# DA_uno_shield_0_3.net
KiCad netlist of a schematic drawn in EAGLE
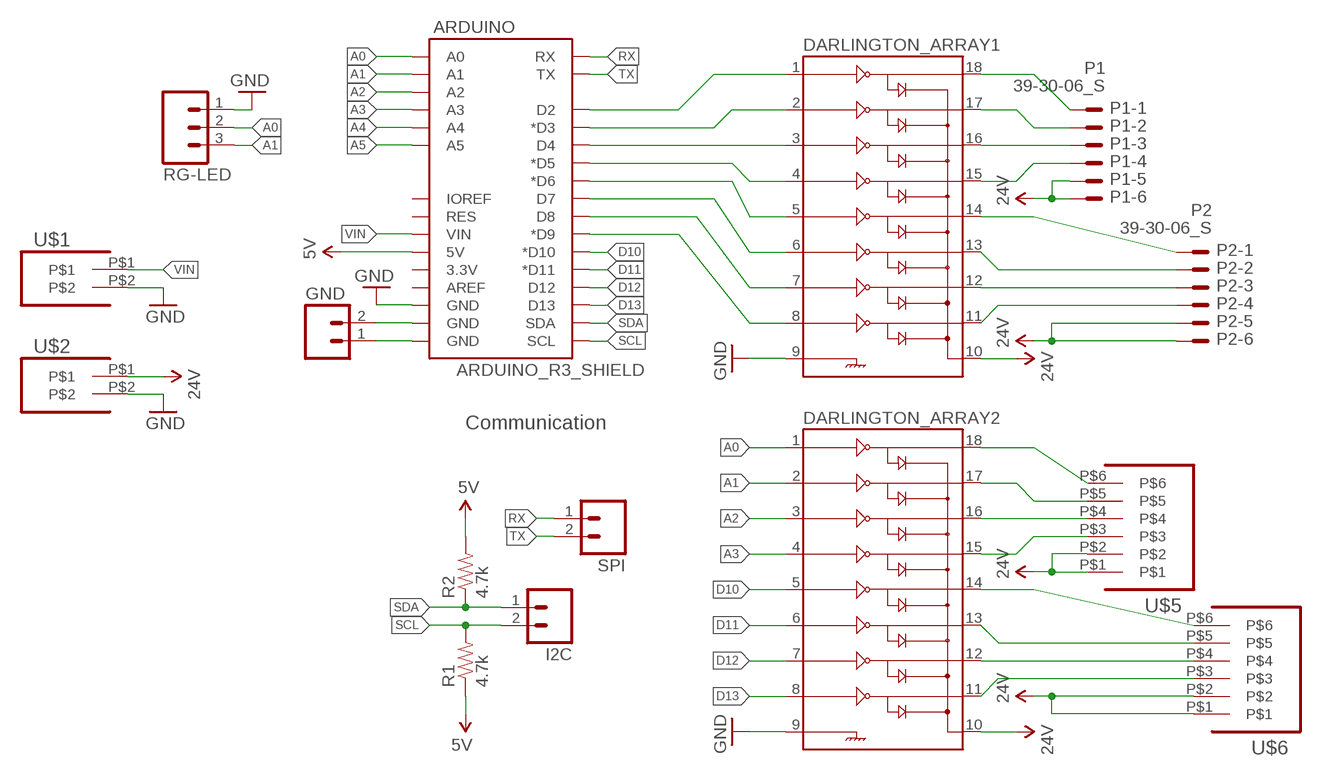
[diagram p0: schematic, sheet 1]

(export (version "E")
  (design (tool "Eeschema 10.0.6"))
  (components
    (comp (ref "ARDUINO")
      (value "ARDUINO_R3_SHIELD")
      (footprint "eagle-import:UNO_R3_SHIELD")
      (libsource (lib "eagle-import") (part "ARDUINO_R3_SHIELD"))
    )
    (comp (ref "DARLINGTON_ARRAY1")
      (value "ULN2803DIP")
      (footprint "eagle-import:DIL18")
      (libsource (lib "eagle-import") (part "ULN2803DIP"))
    )
    (comp (ref "DARLINGTON_ARRAY2")
      (value "ULN2803DIP")
      (footprint "eagle-import:DIL18")
      (libsource (lib "eagle-import") (part "ULN2803DIP"))
    )
    (comp (ref "GND")
      (value "M02LOCK_LONGPADS")
      (footprint "eagle-import:1X02_LOCK_LONGPADS")
      (libsource (lib "eagle-import") (part "M02LOCK_LONGPADS"))
    )
    (comp (ref "I2C")
      (value "M02LOCK_LONGPADS")
      (footprint "eagle-import:1X02_LOCK_LONGPADS")
      (libsource (lib "eagle-import") (part "M02LOCK_LONGPADS"))
    )
    (comp (ref "P1")
      (value "39-30-06_S")
      (footprint "eagle-import:39-30-_06_")
      (libsource (lib "eagle-import") (part "39-30-?06?_S"))
    )
    (comp (ref "P2")
      (value "39-30-06_S")
      (footprint "eagle-import:39-30-_06_")
      (libsource (lib "eagle-import") (part "39-30-?06?_S"))
    )
    (comp (ref "R1")
      (value "4.7k")
      (footprint "eagle-import:AXIAL-0.3-KIT")
      (libsource (lib "eagle-import") (part "RESISTORKIT"))
    )
    (comp (ref "R2")
      (value "4.7k")
      (footprint "eagle-import:AXIAL-0.3-KIT")
      (libsource (lib "eagle-import") (part "RESISTORKIT"))
    )
    (comp (ref "RG-LED")
      (value "M03LONGPADS")
      (footprint "eagle-import:1X03_LONGPADS")
      (libsource (lib "eagle-import") (part "M03LONGPADS"))
    )
    (comp (ref "SPI")
      (value "M02LOCK_LONGPADS")
      (footprint "eagle-import:1X02_LOCK_LONGPADS")
      (libsource (lib "eagle-import") (part "M02LOCK_LONGPADS"))
    )
    (comp (ref "U$1")
      (value "39-29-02")
      (footprint "eagle-import:39-29-_02_")
      (libsource (lib "eagle-import") (part "39-29-?02?"))
    )
    (comp (ref "U$2")
      (value "39-29-02")
      (footprint "eagle-import:39-29-_02_")
      (libsource (lib "eagle-import") (part "39-29-?02?"))
    )
    (comp (ref "U$5")
      (value "39-29-06")
      (footprint "eagle-import:39-29-_06_")
      (libsource (lib "eagle-import") (part "39-29-?06?"))
    )
    (comp (ref "U$6")
      (value "39-29-06")
      (footprint "eagle-import:39-29-_06_")
      (libsource (lib "eagle-import") (part "39-29-?06?"))
    )
  )
  (nets
    (net (code "1") (name "5V") (class "Default")
      (node (ref "ARDUINO") (pin "5V") (pinfunction "5V_5V") (pintype "bidirectional"))
      (node (ref "R1") (pin "P$1") (pinfunction "1_P$1") (pintype "passive"))
      (node (ref "R2") (pin "P$2") (pinfunction "2_P$2") (pintype "passive"))
    )
    (net (code "2") (name "24V") (class "Default")
      (node (ref "DARLINGTON_ARRAY1") (pin "10") (pinfunction "10_10") (pintype "bidirectional"))
      (node (ref "DARLINGTON_ARRAY2") (pin "10") (pinfunction "10_10") (pintype "bidirectional"))
      (node (ref "P1") (pin "5") (pinfunction "P_5") (pintype "passive"))
      (node (ref "P1") (pin "6") (pinfunction "P_6") (pintype "passive"))
      (node (ref "P2") (pin "5") (pinfunction "P_5") (pintype "passive"))
      (node (ref "P2") (pin "6") (pinfunction "P_6") (pintype "passive"))
      (node (ref "U$2") (pin "P$1") (pinfunction "P$1_P$1") (pintype "bidirectional"))
      (node (ref "U$5") (pin "P$1") (pinfunction "P$1_P$1") (pintype "bidirectional"))
      (node (ref "U$5") (pin "P$2") (pinfunction "P$2_P$2") (pintype "bidirectional"))
      (node (ref "U$6") (pin "P$1") (pinfunction "P$1_P$1") (pintype "bidirectional"))
      (node (ref "U$6") (pin "P$2") (pinfunction "P$2_P$2") (pintype "bidirectional"))
    )
    (net (code "3") (name "A0") (class "Default")
      (node (ref "ARDUINO") (pin "A0") (pinfunction "A0_A0") (pintype "bidirectional"))
      (node (ref "DARLINGTON_ARRAY2") (pin "1") (pinfunction "1_1") (pintype "bidirectional"))
      (node (ref "RG-LED") (pin "2") (pinfunction "2_2") (pintype "passive"))
    )
    (net (code "4") (name "A1") (class "Default")
      (node (ref "ARDUINO") (pin "A1") (pinfunction "A1_A1") (pintype "bidirectional"))
      (node (ref "DARLINGTON_ARRAY2") (pin "2") (pinfunction "2_2") (pintype "bidirectional"))
      (node (ref "RG-LED") (pin "3") (pinfunction "3_3") (pintype "passive"))
    )
    (net (code "5") (name "A2") (class "Default")
      (node (ref "ARDUINO") (pin "A2") (pinfunction "A2_A2") (pintype "bidirectional"))
      (node (ref "DARLINGTON_ARRAY2") (pin "3") (pinfunction "3_3") (pintype "bidirectional"))
    )
    (net (code "6") (name "A3") (class "Default")
      (node (ref "ARDUINO") (pin "A3") (pinfunction "A3_A3") (pintype "bidirectional"))
      (node (ref "DARLINGTON_ARRAY2") (pin "4") (pinfunction "4_4") (pintype "bidirectional"))
    )
    (net (code "7") (name "A4") (class "Default")
      (node (ref "ARDUINO") (pin "A4") (pinfunction "A4_A4") (pintype "bidirectional"))
    )
    (net (code "8") (name "A5") (class "Default")
      (node (ref "ARDUINO") (pin "A5") (pinfunction "A5_A5") (pintype "bidirectional"))
    )
    (net (code "9") (name "D10") (class "Default")
      (node (ref "ARDUINO") (pin "D10") (pinfunction "*D10_D10") (pintype "bidirectional"))
      (node (ref "DARLINGTON_ARRAY2") (pin "5") (pinfunction "5_5") (pintype "bidirectional"))
    )
    (net (code "10") (name "D11") (class "Default")
      (node (ref "ARDUINO") (pin "D11") (pinfunction "*D11_D11") (pintype "bidirectional"))
      (node (ref "DARLINGTON_ARRAY2") (pin "6") (pinfunction "6_6") (pintype "bidirectional"))
    )
    (net (code "11") (name "D12") (class "Default")
      (node (ref "ARDUINO") (pin "D12") (pinfunction "D12_D12") (pintype "bidirectional"))
      (node (ref "DARLINGTON_ARRAY2") (pin "7") (pinfunction "7_7") (pintype "bidirectional"))
    )
    (net (code "12") (name "D13") (class "Default")
      (node (ref "ARDUINO") (pin "D13") (pinfunction "D13_D13") (pintype "bidirectional"))
      (node (ref "DARLINGTON_ARRAY2") (pin "8") (pinfunction "8_8") (pintype "bidirectional"))
    )
    (net (code "13") (name "GND") (class "Default")
      (node (ref "ARDUINO") (pin "GND@2") (pinfunction "GND_GND@2") (pintype "bidirectional"))
      (node (ref "DARLINGTON_ARRAY1") (pin "9") (pinfunction "9_9") (pintype "bidirectional"))
      (node (ref "DARLINGTON_ARRAY2") (pin "9") (pinfunction "9_9") (pintype "bidirectional"))
      (node (ref "RG-LED") (pin "1") (pinfunction "1_1") (pintype "passive"))
      (node (ref "U$1") (pin "P$2") (pinfunction "P$2_P$2") (pintype "bidirectional"))
      (node (ref "U$2") (pin "P$2") (pinfunction "P$2_P$2") (pintype "bidirectional"))
    )
    (net (code "14") (name "Net-(ARDUINO-*D3)") (class "Default")
      (node (ref "ARDUINO") (pin "D3") (pinfunction "*D3_D3") (pintype "bidirectional"))
      (node (ref "DARLINGTON_ARRAY1") (pin "2") (pinfunction "2_2") (pintype "bidirectional"))
    )
    (net (code "15") (name "Net-(ARDUINO-*D5)") (class "Default")
      (node (ref "ARDUINO") (pin "D5") (pinfunction "*D5_D5") (pintype "bidirectional"))
      (node (ref "DARLINGTON_ARRAY1") (pin "4") (pinfunction "4_4") (pintype "bidirectional"))
    )
    (net (code "16") (name "Net-(ARDUINO-*D6)") (class "Default")
      (node (ref "ARDUINO") (pin "D6") (pinfunction "*D6_D6") (pintype "bidirectional"))
      (node (ref "DARLINGTON_ARRAY1") (pin "5") (pinfunction "5_5") (pintype "bidirectional"))
    )
    (net (code "17") (name "Net-(ARDUINO-*D9)") (class "Default")
      (node (ref "ARDUINO") (pin "D9") (pinfunction "*D9_D9") (pintype "bidirectional"))
      (node (ref "DARLINGTON_ARRAY1") (pin "8") (pinfunction "8_8") (pintype "bidirectional"))
    )
    (net (code "18") (name "Net-(ARDUINO-GND-PadGND@0)") (class "Default")
      (node (ref "ARDUINO") (pin "GND@0") (pinfunction "GND_GND@0") (pintype "bidirectional"))
      (node (ref "GND") (pin "1") (pinfunction "1_1") (pintype "passive"))
    )
    (net (code "19") (name "Net-(ARDUINO-GND-PadGND@1)") (class "Default")
      (node (ref "ARDUINO") (pin "GND@1") (pinfunction "GND_GND@1") (pintype "bidirectional"))
      (node (ref "GND") (pin "2") (pinfunction "2_2") (pintype "passive"))
    )
    (net (code "20") (name "Net-(ARDUINO-PadD2)") (class "Default")
      (node (ref "ARDUINO") (pin "D2") (pinfunction "D2_D2") (pintype "bidirectional"))
      (node (ref "DARLINGTON_ARRAY1") (pin "1") (pinfunction "1_1") (pintype "bidirectional"))
    )
    (net (code "21") (name "Net-(ARDUINO-PadD4)") (class "Default")
      (node (ref "ARDUINO") (pin "D4") (pinfunction "D4_D4") (pintype "bidirectional"))
      (node (ref "DARLINGTON_ARRAY1") (pin "3") (pinfunction "3_3") (pintype "bidirectional"))
    )
    (net (code "22") (name "Net-(ARDUINO-PadD7)") (class "Default")
      (node (ref "ARDUINO") (pin "D7") (pinfunction "D7_D7") (pintype "bidirectional"))
      (node (ref "DARLINGTON_ARRAY1") (pin "6") (pinfunction "6_6") (pintype "bidirectional"))
    )
    (net (code "23") (name "Net-(ARDUINO-PadD8)") (class "Default")
      (node (ref "ARDUINO") (pin "D8") (pinfunction "D8_D8") (pintype "bidirectional"))
      (node (ref "DARLINGTON_ARRAY1") (pin "7") (pinfunction "7_7") (pintype "bidirectional"))
    )
    (net (code "24") (name "Net-(DARLINGTON_ARRAY2-Pad11)") (class "Default")
      (node (ref "DARLINGTON_ARRAY2") (pin "11") (pinfunction "11_11") (pintype "bidirectional"))
      (node (ref "U$6") (pin "P$3") (pinfunction "P$3_P$3") (pintype "bidirectional"))
    )
    (net (code "25") (name "Net-(DARLINGTON_ARRAY2-Pad12)") (class "Default")
      (node (ref "DARLINGTON_ARRAY2") (pin "12") (pinfunction "12_12") (pintype "bidirectional"))
      (node (ref "U$6") (pin "P$4") (pinfunction "P$4_P$4") (pintype "bidirectional"))
    )
    (net (code "26") (name "Net-(DARLINGTON_ARRAY2-Pad13)") (class "Default")
      (node (ref "DARLINGTON_ARRAY2") (pin "13") (pinfunction "13_13") (pintype "bidirectional"))
      (node (ref "U$6") (pin "P$5") (pinfunction "P$5_P$5") (pintype "bidirectional"))
    )
    (net (code "27") (name "Net-(DARLINGTON_ARRAY2-Pad14)") (class "Default")
      (node (ref "DARLINGTON_ARRAY2") (pin "14") (pinfunction "14_14") (pintype "bidirectional"))
      (node (ref "U$6") (pin "P$6") (pinfunction "P$6_P$6") (pintype "bidirectional"))
    )
    (net (code "28") (name "Net-(DARLINGTON_ARRAY2-Pad15)") (class "Default")
      (node (ref "DARLINGTON_ARRAY2") (pin "15") (pinfunction "15_15") (pintype "bidirectional"))
      (node (ref "U$5") (pin "P$3") (pinfunction "P$3_P$3") (pintype "bidirectional"))
    )
    (net (code "29") (name "Net-(DARLINGTON_ARRAY2-Pad16)") (class "Default")
      (node (ref "DARLINGTON_ARRAY2") (pin "16") (pinfunction "16_16") (pintype "bidirectional"))
      (node (ref "U$5") (pin "P$4") (pinfunction "P$4_P$4") (pintype "bidirectional"))
    )
    (net (code "30") (name "Net-(DARLINGTON_ARRAY2-Pad17)") (class "Default")
      (node (ref "DARLINGTON_ARRAY2") (pin "17") (pinfunction "17_17") (pintype "bidirectional"))
      (node (ref "U$5") (pin "P$5") (pinfunction "P$5_P$5") (pintype "bidirectional"))
    )
    (net (code "31") (name "Net-(DARLINGTON_ARRAY2-Pad18)") (class "Default")
      (node (ref "DARLINGTON_ARRAY2") (pin "18") (pinfunction "18_18") (pintype "bidirectional"))
      (node (ref "U$5") (pin "P$6") (pinfunction "P$6_P$6") (pintype "bidirectional"))
    )
    (net (code "32") (name "Net-(P1A-P)") (class "Default")
      (node (ref "DARLINGTON_ARRAY1") (pin "18") (pinfunction "18_18") (pintype "bidirectional"))
      (node (ref "P1") (pin "1") (pinfunction "P_1") (pintype "passive"))
    )
    (net (code "33") (name "Net-(P1B-P)") (class "Default")
      (node (ref "DARLINGTON_ARRAY1") (pin "17") (pinfunction "17_17") (pintype "bidirectional"))
      (node (ref "P1") (pin "2") (pinfunction "P_2") (pintype "passive"))
    )
    (net (code "34") (name "Net-(P1C-P)") (class "Default")
      (node (ref "DARLINGTON_ARRAY1") (pin "16") (pinfunction "16_16") (pintype "bidirectional"))
      (node (ref "P1") (pin "3") (pinfunction "P_3") (pintype "passive"))
    )
    (net (code "35") (name "Net-(P1D-P)") (class "Default")
      (node (ref "DARLINGTON_ARRAY1") (pin "15") (pinfunction "15_15") (pintype "bidirectional"))
      (node (ref "P1") (pin "4") (pinfunction "P_4") (pintype "passive"))
    )
    (net (code "36") (name "Net-(P2A-P)") (class "Default")
      (node (ref "DARLINGTON_ARRAY1") (pin "14") (pinfunction "14_14") (pintype "bidirectional"))
      (node (ref "P2") (pin "1") (pinfunction "P_1") (pintype "passive"))
    )
    (net (code "37") (name "Net-(P2B-P)") (class "Default")
      (node (ref "DARLINGTON_ARRAY1") (pin "13") (pinfunction "13_13") (pintype "bidirectional"))
      (node (ref "P2") (pin "2") (pinfunction "P_2") (pintype "passive"))
    )
    (net (code "38") (name "Net-(P2C-P)") (class "Default")
      (node (ref "DARLINGTON_ARRAY1") (pin "12") (pinfunction "12_12") (pintype "bidirectional"))
      (node (ref "P2") (pin "3") (pinfunction "P_3") (pintype "passive"))
    )
    (net (code "39") (name "Net-(P2D-P)") (class "Default")
      (node (ref "DARLINGTON_ARRAY1") (pin "11") (pinfunction "11_11") (pintype "bidirectional"))
      (node (ref "P2") (pin "4") (pinfunction "P_4") (pintype "passive"))
    )
    (net (code "40") (name "RX") (class "Default")
      (node (ref "ARDUINO") (pin "RX") (pinfunction "RX_RX") (pintype "bidirectional"))
      (node (ref "SPI") (pin "1") (pinfunction "1_1") (pintype "passive"))
    )
    (net (code "41") (name "SCL") (class "Default")
      (node (ref "ARDUINO") (pin "SCL") (pinfunction "SCL_SCL") (pintype "bidirectional"))
      (node (ref "I2C") (pin "2") (pinfunction "2_2") (pintype "passive"))
      (node (ref "R1") (pin "P$2") (pinfunction "2_P$2") (pintype "passive"))
    )
    (net (code "42") (name "SDA") (class "Default")
      (node (ref "ARDUINO") (pin "SDA") (pinfunction "SDA_SDA") (pintype "bidirectional"))
      (node (ref "I2C") (pin "1") (pinfunction "1_1") (pintype "passive"))
      (node (ref "R2") (pin "P$1") (pinfunction "1_P$1") (pintype "passive"))
    )
    (net (code "43") (name "TX") (class "Default")
      (node (ref "ARDUINO") (pin "TX") (pinfunction "TX_TX") (pintype "bidirectional"))
      (node (ref "SPI") (pin "2") (pinfunction "2_2") (pintype "passive"))
    )
    (net (code "44") (name "VIN") (class "Default")
      (node (ref "ARDUINO") (pin "VIN") (pinfunction "VIN_VIN") (pintype "bidirectional"))
      (node (ref "U$1") (pin "P$1") (pinfunction "P$1_P$1") (pintype "bidirectional"))
    )
    (net (code "45") (name "unconnected-(ARDUINO-Pad3.3V)") (class "Default")
      (node (ref "ARDUINO") (pin "3.3V") (pinfunction "3.3V_3.3V") (pintype "bidirectional"))
    )
    (net (code "46") (name "unconnected-(ARDUINO-PadAREF)") (class "Default")
      (node (ref "ARDUINO") (pin "AREF") (pinfunction "AREF_AREF") (pintype "bidirectional"))
    )
    (net (code "47") (name "unconnected-(ARDUINO-PadIOREF)") (class "Default")
      (node (ref "ARDUINO") (pin "IOREF") (pinfunction "IOREF_IOREF") (pintype "bidirectional"))
    )
    (net (code "48") (name "unconnected-(ARDUINO-PadRES)") (class "Default")
      (node (ref "ARDUINO") (pin "RES") (pinfunction "RES_RES") (pintype "bidirectional"))
    )
  )
)
